# 04_BLE_WIFI_module.net
KiCad netlist of a schematic drawn in Altium Designer
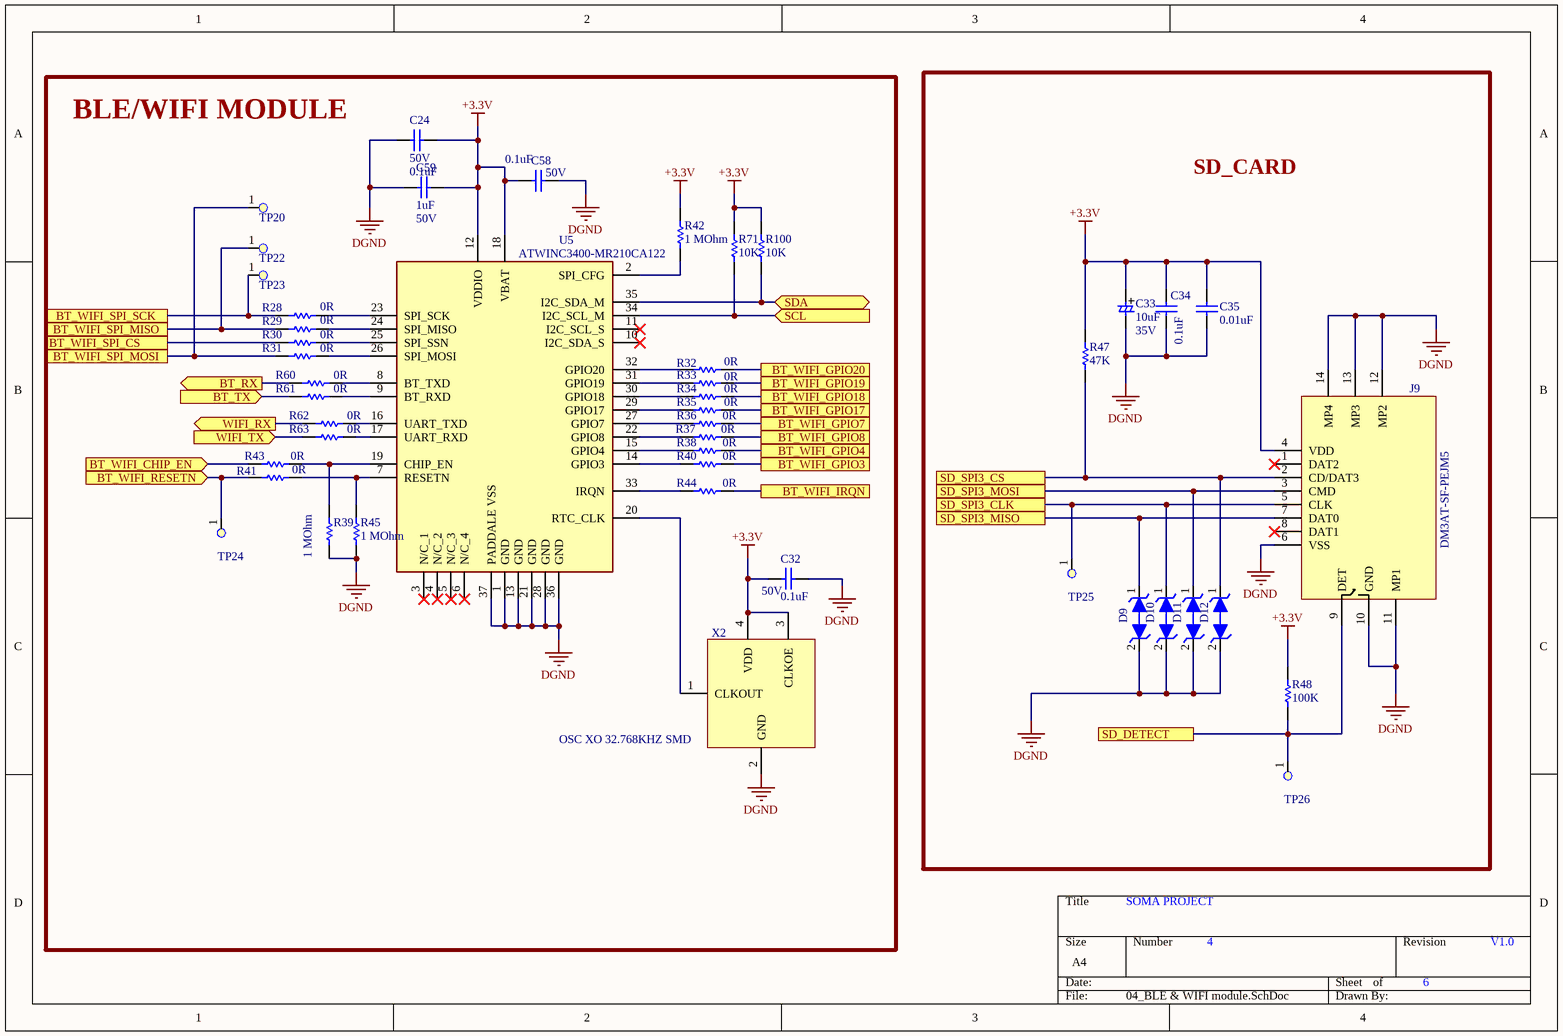
[diagram p0: 04_BLE & WIFI module.SchDoc]

(export (version "E")
  (design (tool "Eeschema 10.0.6"))
  (components
    (comp (ref "C24")
      (value "0.1uF")
      (footprint "C0402")
      (description "CAP CER 0.1UF 50V X7R 0402")
      (fields
        (field (name "MANUFACTURER") "AVX")
        (field (name "DISTRIBUTOR PART NUMBER") "581-04025C104KAT2A")
        (field (name "RATING") "50V")
      )
      (libsource (lib "SOMA_15072021") (part "CAP CER 0.1UF 50V X7R 0402"))
    )
    (comp (ref "C32")
      (value "0.1uF")
      (footprint "C0402")
      (description "CAP CER 0.1UF 50V X7R 0402")
      (fields
        (field (name "MANUFACTURER") "AVX")
        (field (name "DISTRIBUTOR PART NUMBER") "581-04025C104KAT2A")
        (field (name "RATING") "50V")
      )
      (libsource (lib "SOMA_15072021") (part "CAP CER 0.1UF 50V X7R 0402"))
    )
    (comp (ref "C33")
      (value "10uF")
      (footprint "CAPAE430X540N")
      (description "CAP ALUM 10UF 20% 35V SMD")
      (fields
        (field (name "MANUFACTURER") "Panasonic")
        (field (name "MANUFACTURER PART NUMBER") "EEE-1VA100WR")
        (field (name "RATING") "35V")
      )
      (libsource (lib "SOMA_15072021") (part "CAP ALUM 10UF 20% 35V SMD"))
    )
    (comp (ref "C34")
      (value "0.1uF")
      (footprint "C0603")
      (description "CAP CER 0.1UF 10V X7R 0603")
      (fields
        (field (name "MANUFACTURER") "Würth Elektronik")
        (field (name "DISTRIBUTOR PART NUMBER") "732-7939-1-ND")
      )
      (libsource (lib "SOMA_1") (part "CAP CER 0.1UF 10V X7R 0603"))
    )
    (comp (ref "C35")
      (value "0.01uF")
      (footprint "C0402")
      (description "CAP CER 0.01uF 50V X7R 0402")
      (fields
        (field (name "MANUFACTURER") "Yageo")
        (field (name "MANUFACTURER PART NUMBER") "CC0402KRX7R9BB103")
      )
      (libsource (lib "SOMA_15072021") (part "CAP CER 0.01uF 50V X7R 0402"))
    )
    (comp (ref "C58")
      (value "0.1uF")
      (footprint "C0402")
      (description "CAP CER 0.1UF 50V X7R 0402")
      (fields
        (field (name "MANUFACTURER") "AVX")
        (field (name "DISTRIBUTOR PART NUMBER") "581-04025C104KAT2A")
        (field (name "RATING") "50V")
      )
      (libsource (lib "SOMA_15072021") (part "CAP CER 0.1UF 50V X7R 0402"))
    )
    (comp (ref "C59")
      (value "1uF")
      (footprint "C0603")
      (description "CAP CER 1UF 50V X5R 0603")
      (fields
        (field (name "MANUFACTURER") "Taiyo Yuden")
        (field (name "DISTRIBUTOR PART NUMBER") "587-2400-2-ND")
        (field (name "RATING") "50V")
      )
      (libsource (lib "SOMA_15072021") (part "CAP CER 1UF 50V X5R 0603"))
    )
    (comp (ref "D9")
      (value "TVS DIODE 3.3VWM 11.5VC SOD923")
      (footprint "SOD1006X40N_BI")
      (description "11.5V Clamp 2A (8/20µs) Ipp Tvs Diode Surface Mount SOD-923")
      (fields
        (field (name "MANUFACTURER PART NUMBER") "ESD9B3.3ST5G")
        (field (name "MANUFACTURER") "ON Semiconductor")
      )
      (libsource (lib "SOMA_15072021") (part "TVS DIODE 3.3VWM 11.5VC SOD923"))
    )
    (comp (ref "D10")
      (value "TVS DIODE 3.3VWM 11.5VC SOD923")
      (footprint "SOD1006X40N_BI")
      (description "11.5V Clamp 2A (8/20µs) Ipp Tvs Diode Surface Mount SOD-923")
      (fields
        (field (name "MANUFACTURER PART NUMBER") "ESD9B3.3ST5G")
        (field (name "MANUFACTURER") "ON Semiconductor")
      )
      (libsource (lib "SOMA_15072021") (part "TVS DIODE 3.3VWM 11.5VC SOD923"))
    )
    (comp (ref "D11")
      (value "TVS DIODE 3.3VWM 11.5VC SOD923")
      (footprint "SOD1006X40N_BI")
      (description "11.5V Clamp 2A (8/20µs) Ipp Tvs Diode Surface Mount SOD-923")
      (fields
        (field (name "MANUFACTURER PART NUMBER") "ESD9B3.3ST5G")
        (field (name "MANUFACTURER") "ON Semiconductor")
      )
      (libsource (lib "SOMA_15072021") (part "TVS DIODE 3.3VWM 11.5VC SOD923"))
    )
    (comp (ref "D12")
      (value "TVS DIODE 3.3VWM 11.5VC SOD923")
      (footprint "SOD1006X40N_BI")
      (description "11.5V Clamp 2A (8/20µs) Ipp Tvs Diode Surface Mount SOD-923")
      (fields
        (field (name "MANUFACTURER PART NUMBER") "ESD9B3.3ST5G")
        (field (name "MANUFACTURER") "ON Semiconductor")
      )
      (libsource (lib "SOMA_15072021") (part "TVS DIODE 3.3VWM 11.5VC SOD923"))
    )
    (comp (ref "J9")
      (value "DM3AT-SF-PEJM5")
      (footprint "HIROSE_DM3AT-SF-PEJM5")
      (description "CONN MICRO SD CARD PUSH-PUSH R/A")
      (fields
        (field (name "DISTRIBUTOR PART NUMBER") "HR1964CT-ND")
        (field (name "MANUFACTURER") "Hirose Electric Co Ltd")
      )
      (libsource (lib "SOMA_15072021") (part "CONN MICRO SD CARD PUSH-PUSH R/A"))
    )
    (comp (ref "R28")
      (value "0R")
      (footprint "R0402")
      (description "0 Ohms Jumper 0.063W, 1/16W Chip Resistor 0402 (1005 Metric) Moisture Resistant Thick Film")
      (fields (field (name "MANUFACTURER") "Yageo") (field (name "DISTRIBUTOR PART NUMBER") "YAG1279TR-ND"))
      (libsource (lib "SOMA_1") (part "RES SMD 0 OHM JUMPER 1/16W 0402"))
    )
    (comp (ref "R29")
      (value "0R")
      (footprint "R0402")
      (description "0 Ohms Jumper 0.063W, 1/16W Chip Resistor 0402 (1005 Metric) Moisture Resistant Thick Film")
      (fields (field (name "MANUFACTURER") "Yageo") (field (name "DISTRIBUTOR PART NUMBER") "YAG1279TR-ND"))
      (libsource (lib "SOMA_1") (part "RES SMD 0 OHM JUMPER 1/16W 0402"))
    )
    (comp (ref "R30")
      (value "0R")
      (footprint "R0402")
      (description "0 Ohms Jumper 0.063W, 1/16W Chip Resistor 0402 (1005 Metric) Moisture Resistant Thick Film")
      (fields (field (name "MANUFACTURER") "Yageo") (field (name "DISTRIBUTOR PART NUMBER") "YAG1279TR-ND"))
      (libsource (lib "SOMA_1") (part "RES SMD 0 OHM JUMPER 1/16W 0402"))
    )
    (comp (ref "R31")
      (value "0R")
      (footprint "R0402")
      (description "0 Ohms Jumper 0.063W, 1/16W Chip Resistor 0402 (1005 Metric) Moisture Resistant Thick Film")
      (fields (field (name "MANUFACTURER") "Yageo") (field (name "DISTRIBUTOR PART NUMBER") "YAG1279TR-ND"))
      (libsource (lib "SOMA_1") (part "RES SMD 0 OHM JUMPER 1/16W 0402"))
    )
    (comp (ref "R32")
      (value "0R")
      (footprint "R0402")
      (description "0 Ohms Jumper 0.063W, 1/16W Chip Resistor 0402 (1005 Metric) Moisture Resistant Thick Film")
      (fields (field (name "MANUFACTURER") "Yageo") (field (name "DISTRIBUTOR PART NUMBER") "YAG1279TR-ND"))
      (libsource (lib "SOMA_1") (part "RES SMD 0 OHM JUMPER 1/16W 0402"))
    )
    (comp (ref "R33")
      (value "0R")
      (footprint "R0402")
      (description "0 Ohms Jumper 0.063W, 1/16W Chip Resistor 0402 (1005 Metric) Moisture Resistant Thick Film")
      (fields (field (name "MANUFACTURER") "Yageo") (field (name "DISTRIBUTOR PART NUMBER") "YAG1279TR-ND"))
      (libsource (lib "SOMA_1") (part "RES SMD 0 OHM JUMPER 1/16W 0402"))
    )
    (comp (ref "R34")
      (value "0R")
      (footprint "R0402")
      (description "0 Ohms Jumper 0.063W, 1/16W Chip Resistor 0402 (1005 Metric) Moisture Resistant Thick Film")
      (fields (field (name "MANUFACTURER") "Yageo") (field (name "DISTRIBUTOR PART NUMBER") "YAG1279TR-ND"))
      (libsource (lib "SOMA_1") (part "RES SMD 0 OHM JUMPER 1/16W 0402"))
    )
    (comp (ref "R35")
      (value "0R")
      (footprint "R0402")
      (description "0 Ohms Jumper 0.063W, 1/16W Chip Resistor 0402 (1005 Metric) Moisture Resistant Thick Film")
      (fields (field (name "MANUFACTURER") "Yageo") (field (name "DISTRIBUTOR PART NUMBER") "YAG1279TR-ND"))
      (libsource (lib "SOMA_1") (part "RES SMD 0 OHM JUMPER 1/16W 0402"))
    )
    (comp (ref "R36")
      (value "0R")
      (footprint "R0402")
      (description "0 Ohms Jumper 0.063W, 1/16W Chip Resistor 0402 (1005 Metric) Moisture Resistant Thick Film")
      (fields (field (name "MANUFACTURER") "Yageo") (field (name "DISTRIBUTOR PART NUMBER") "YAG1279TR-ND"))
      (libsource (lib "SOMA_1") (part "RES SMD 0 OHM JUMPER 1/16W 0402"))
    )
    (comp (ref "R37")
      (value "0R")
      (footprint "R0402")
      (description "0 Ohms Jumper 0.063W, 1/16W Chip Resistor 0402 (1005 Metric) Moisture Resistant Thick Film")
      (fields (field (name "MANUFACTURER") "Yageo") (field (name "DISTRIBUTOR PART NUMBER") "YAG1279TR-ND"))
      (libsource (lib "SOMA_1") (part "RES SMD 0 OHM JUMPER 1/16W 0402"))
    )
    (comp (ref "R38")
      (value "0R")
      (footprint "R0402")
      (description "0 Ohms Jumper 0.063W, 1/16W Chip Resistor 0402 (1005 Metric) Moisture Resistant Thick Film")
      (fields (field (name "MANUFACTURER") "Yageo") (field (name "DISTRIBUTOR PART NUMBER") "YAG1279TR-ND"))
      (libsource (lib "SOMA_1") (part "RES SMD 0 OHM JUMPER 1/16W 0402"))
    )
    (comp (ref "R39")
      (value "1 MOhm")
      (footprint "R0603")
      (description "RES 1M OHM 1% 1/10W 0603")
      (fields
        (field (name "MANUFACTURER PART NUMBER") "RC0603FR-131ML")
        (field (name "MANUFACTURER") "Yageo")
      )
      (libsource (lib "SOMA_1") (part "RES 1M OHM 1% 1/10W 0603"))
    )
    (comp (ref "R40")
      (value "0R")
      (footprint "R0402")
      (description "0 Ohms Jumper 0.063W, 1/16W Chip Resistor 0402 (1005 Metric) Moisture Resistant Thick Film")
      (fields (field (name "MANUFACTURER") "Yageo") (field (name "DISTRIBUTOR PART NUMBER") "YAG1279TR-ND"))
      (libsource (lib "SOMA_1") (part "RES SMD 0 OHM JUMPER 1/16W 0402"))
    )
    (comp (ref "R41")
      (value "0R")
      (footprint "R0402")
      (description "0 Ohms Jumper 0.063W, 1/16W Chip Resistor 0402 (1005 Metric) Moisture Resistant Thick Film")
      (fields (field (name "MANUFACTURER") "Yageo") (field (name "DISTRIBUTOR PART NUMBER") "YAG1279TR-ND"))
      (libsource (lib "SOMA_1") (part "RES SMD 0 OHM JUMPER 1/16W 0402"))
    )
    (comp (ref "R42")
      (value "1 MOhm")
      (footprint "R0603")
      (description "RES 1M OHM 1% 1/10W 0603")
      (fields
        (field (name "MANUFACTURER PART NUMBER") "RC0603FR-131ML")
        (field (name "MANUFACTURER") "Yageo")
      )
      (libsource (lib "SOMA_1") (part "RES 1M OHM 1% 1/10W 0603"))
    )
    (comp (ref "R43")
      (value "0R")
      (footprint "R0402")
      (description "0 Ohms Jumper 0.063W, 1/16W Chip Resistor 0402 (1005 Metric) Moisture Resistant Thick Film")
      (fields (field (name "MANUFACTURER") "Yageo") (field (name "DISTRIBUTOR PART NUMBER") "YAG1279TR-ND"))
      (libsource (lib "SOMA_1") (part "RES SMD 0 OHM JUMPER 1/16W 0402"))
    )
    (comp (ref "R44")
      (value "0R")
      (footprint "R0402")
      (description "0 Ohms Jumper 0.063W, 1/16W Chip Resistor 0402 (1005 Metric) Moisture Resistant Thick Film")
      (fields (field (name "MANUFACTURER") "Yageo") (field (name "DISTRIBUTOR PART NUMBER") "YAG1279TR-ND"))
      (libsource (lib "SOMA_1") (part "RES SMD 0 OHM JUMPER 1/16W 0402"))
    )
    (comp (ref "R45")
      (value "1 MOhm")
      (footprint "R0603")
      (description "RES 1M OHM 1% 1/10W 0603")
      (fields
        (field (name "MANUFACTURER PART NUMBER") "RC0603FR-131ML")
        (field (name "MANUFACTURER") "Yageo")
      )
      (libsource (lib "SOMA_1") (part "RES 1M OHM 1% 1/10W 0603"))
    )
    (comp (ref "R47")
      (value "47K")
      (footprint "R0402")
      (description "RES SMD 47K OHM 5% 1/10W 0402")
      (fields
        (field (name "MANUFACTURER PART NUMBER") "ERJ-2GEJ473X")
        (field (name "DISTRIBUTOR PART NUMBER") "P47KJCT-ND")
      )
      (libsource (lib "SOMA_15072021") (part "RES SMD 47K OHM 5% 1/10W 0402"))
    )
    (comp (ref "R48")
      (value "100K")
      (footprint "R0402")
      (description "100 kOhms ±1% 0.1W, 1/10W Chip Resistor 0402 (1005 Metric) Automotive AEC-Q200 Thick Film")
      (fields
        (field (name "MANUFACTURER") "Panasonic Electronic Components")
        (field (name "MANUFACTURER PART NUMBER") "ERJ-2RKF1003X")
      )
      (libsource (lib "SOMA_15072021") (part "RES SMD 100K OHM 1% 1/10W 0402"))
    )
    (comp (ref "R60")
      (value "0R")
      (footprint "R0402")
      (description "0 Ohms Jumper 0.063W, 1/16W Chip Resistor 0402 (1005 Metric) Moisture Resistant Thick Film")
      (fields (field (name "MANUFACTURER") "Yageo") (field (name "DISTRIBUTOR PART NUMBER") "YAG1279TR-ND"))
      (libsource (lib "SOMA_1") (part "RES SMD 0 OHM JUMPER 1/16W 0402"))
    )
    (comp (ref "R61")
      (value "0R")
      (footprint "R0402")
      (description "0 Ohms Jumper 0.063W, 1/16W Chip Resistor 0402 (1005 Metric) Moisture Resistant Thick Film")
      (fields (field (name "MANUFACTURER") "Yageo") (field (name "DISTRIBUTOR PART NUMBER") "YAG1279TR-ND"))
      (libsource (lib "SOMA_1") (part "RES SMD 0 OHM JUMPER 1/16W 0402"))
    )
    (comp (ref "R62")
      (value "0R")
      (footprint "R0402")
      (description "0 Ohms Jumper 0.063W, 1/16W Chip Resistor 0402 (1005 Metric) Moisture Resistant Thick Film")
      (fields (field (name "MANUFACTURER") "Yageo") (field (name "DISTRIBUTOR PART NUMBER") "YAG1279TR-ND"))
      (libsource (lib "SOMA_1") (part "RES SMD 0 OHM JUMPER 1/16W 0402"))
    )
    (comp (ref "R63")
      (value "0R")
      (footprint "R0402")
      (description "0 Ohms Jumper 0.063W, 1/16W Chip Resistor 0402 (1005 Metric) Moisture Resistant Thick Film")
      (fields (field (name "MANUFACTURER") "Yageo") (field (name "DISTRIBUTOR PART NUMBER") "YAG1279TR-ND"))
      (libsource (lib "SOMA_1") (part "RES SMD 0 OHM JUMPER 1/16W 0402"))
    )
    (comp (ref "R71")
      (value "10K")
      (footprint "R0402")
      (description "10 kOhms ±1% 0.1W, 1/10W Chip Resistor 0402 (1005 Metric) Automotive AEC-Q200 Thick Film")
      (fields
        (field (name "MANUFACTURER") "Panasonic Electronic Components")
        (field (name "DISTRIBUTOR PART NUMBER") "P10.0KLCT-ND")
      )
      (libsource (lib "Daughtercard_Library") (part "RES SMD 10K OHM 1% 1/10W 0402"))
    )
    (comp (ref "R100")
      (value "10K")
      (footprint "R0402")
      (description "10 kOhms ±1% 0.1W, 1/10W Chip Resistor 0402 (1005 Metric) Automotive AEC-Q200 Thick Film")
      (fields
        (field (name "MANUFACTURER") "Panasonic Electronic Components")
        (field (name "DISTRIBUTOR PART NUMBER") "P10.0KLCT-ND")
      )
      (libsource (lib "Daughtercard_Library") (part "RES SMD 10K OHM 1% 1/10W 0402"))
    )
    (comp (ref "TP20")
      (value "Test Point,1.6mm Diameter,SMD")
      (footprint "TP_63C")
      (libsource (lib "SOMA_1") (part "Test Point,1.6mm Diameter,SMD"))
    )
    (comp (ref "TP22")
      (value "Test Point,1.6mm Diameter,SMD")
      (footprint "TP_63C")
      (libsource (lib "SOMA_1") (part "Test Point,1.6mm Diameter,SMD"))
    )
    (comp (ref "TP23")
      (value "Test Point,1.6mm Diameter,SMD")
      (footprint "TP_63C")
      (libsource (lib "SOMA_1") (part "Test Point,1.6mm Diameter,SMD"))
    )
    (comp (ref "TP24")
      (value "Test Point,1.6mm Diameter,SMD")
      (footprint "TP_63C")
      (libsource (lib "SOMA_1") (part "Test Point,1.6mm Diameter,SMD"))
    )
    (comp (ref "TP25")
      (value "Test Point,1.6mm Diameter,SMD")
      (footprint "TP_63C")
      (libsource (lib "SOMA_1") (part "Test Point,1.6mm Diameter,SMD"))
    )
    (comp (ref "TP26")
      (value "Test Point,1.6mm Diameter,SMD")
      (footprint "TP_63C")
      (libsource (lib "SOMA_1") (part "Test Point,1.6mm Diameter,SMD"))
    )
    (comp (ref "U5")
      (value "ATWINC3400-MR210CA122")
      (footprint "MICROCHIP_ATWINC3400-MR210xA")
      (description "RX TXRX MODULE WIFI CHIP SMD")
      (fields
        (field (name "MANUFACTURER") "Microchip Technology")
        (field (name "DISTRIBUTOR PART NUMBER") "ATWINC3400-MR210CA122-ND")
      )
      (libsource (lib "SOMA_15072021") (part "RX TXRX MODULE WIFI CHIP SMD"))
    )
    (comp (ref "X2")
      (value "OSC XO 32.768KHZ SMD")
      (footprint "XTAL320X150X70-4N")
      (description "32.768 kHz XO (Standard) CMOS Oscillator 1.2V ~ 5.5V Enable/Disable 4-SMD, No Lead")
      (fields
        (field (name "MANUFACTURER") "Micro Crystal AG")
        (field (name "MANUFACTURER PART NUMBER") "OM-7604-C7-32.768KHZ-20PPM-TA-QC")
      )
      (libsource (lib "SOMA_1") (part "OSC XO 32.768KHZ SMD"))
    )
  )
  (nets
    (net (code "1") (name "+3.3V") (class "Default")
      (node (ref "C24") (pin "1") (pinfunction "1_1") (pintype "passive"))
      (node (ref "C32") (pin "2") (pinfunction "2_2") (pintype "passive"))
      (node (ref "C33") (pin "2") (pinfunction "2_2") (pintype "passive"))
      (node (ref "C34") (pin "2") (pinfunction "2_2") (pintype "passive"))
      (node (ref "C35") (pin "2") (pinfunction "2_2") (pintype "passive"))
      (node (ref "C58") (pin "2") (pinfunction "2_2") (pintype "passive"))
      (node (ref "C59") (pin "1") (pinfunction "1_1") (pintype "passive"))
      (node (ref "J9") (pin "4") (pinfunction "VDD_4") (pintype "passive"))
      (node (ref "R100") (pin "2") (pinfunction "2_2") (pintype "passive"))
      (node (ref "R42") (pin "1") (pinfunction "1_1") (pintype "passive"))
      (node (ref "R47") (pin "2") (pinfunction "2_2") (pintype "passive"))
      (node (ref "R48") (pin "2") (pinfunction "2_2") (pintype "passive"))
      (node (ref "R71") (pin "2") (pinfunction "2_2") (pintype "passive"))
      (node (ref "U5") (pin "12") (pinfunction "VDDIO_12") (pintype "power_in"))
      (node (ref "U5") (pin "18") (pinfunction "VBAT_18") (pintype "power_in"))
      (node (ref "X2") (pin "3") (pinfunction "CLKOE_3") (pintype "passive"))
      (node (ref "X2") (pin "4") (pinfunction "VDD_4") (pintype "passive"))
    )
    (net (code "2") (name "/BT_RX") (class "Default")
      (node (ref "R60") (pin "1") (pinfunction "1_1") (pintype "passive"))
    )
    (net (code "3") (name "/BT_TX") (class "Default")
      (node (ref "R61") (pin "1") (pinfunction "1_1") (pintype "passive"))
    )
    (net (code "4") (name "/BT_WIFI_CHIP_EN") (class "Default")
      (node (ref "R43") (pin "1") (pinfunction "1_1") (pintype "passive"))
    )
    (net (code "5") (name "/BT_WIFI_GPIO3") (class "Default")
      (node (ref "R40") (pin "2") (pinfunction "2_2") (pintype "passive"))
    )
    (net (code "6") (name "/BT_WIFI_GPIO4") (class "Default")
      (node (ref "R38") (pin "2") (pinfunction "2_2") (pintype "passive"))
    )
    (net (code "7") (name "/BT_WIFI_GPIO7") (class "Default")
      (node (ref "R36") (pin "2") (pinfunction "2_2") (pintype "passive"))
    )
    (net (code "8") (name "/BT_WIFI_GPIO8") (class "Default")
      (node (ref "R37") (pin "2") (pinfunction "2_2") (pintype "passive"))
    )
    (net (code "9") (name "/BT_WIFI_GPIO17") (class "Default")
      (node (ref "R35") (pin "2") (pinfunction "2_2") (pintype "passive"))
    )
    (net (code "10") (name "/BT_WIFI_GPIO18") (class "Default")
      (node (ref "R34") (pin "2") (pinfunction "2_2") (pintype "passive"))
    )
    (net (code "11") (name "/BT_WIFI_GPIO19") (class "Default")
      (node (ref "R33") (pin "2") (pinfunction "2_2") (pintype "passive"))
    )
    (net (code "12") (name "/BT_WIFI_GPIO20") (class "Default")
      (node (ref "R32") (pin "2") (pinfunction "2_2") (pintype "passive"))
    )
    (net (code "13") (name "/BT_WIFI_IRQN") (class "Default")
      (node (ref "R44") (pin "2") (pinfunction "2_2") (pintype "passive"))
    )
    (net (code "14") (name "/BT_WIFI_RESETN") (class "Default")
      (node (ref "R41") (pin "1") (pinfunction "1_1") (pintype "passive"))
      (node (ref "TP24") (pin "1") (pinfunction "0_1") (pintype "passive"))
    )
    (net (code "15") (name "/BT_WIFI_SPI_CS") (class "Default")
      (node (ref "R30") (pin "1") (pinfunction "1_1") (pintype "passive"))
    )
    (net (code "16") (name "/BT_WIFI_SPI_MISO") (class "Default")
      (node (ref "R29") (pin "1") (pinfunction "1_1") (pintype "passive"))
      (node (ref "TP22") (pin "1") (pinfunction "0_1") (pintype "passive"))
    )
    (net (code "17") (name "/BT_WIFI_SPI_MOSI") (class "Default")
      (node (ref "R31") (pin "1") (pinfunction "1_1") (pintype "passive"))
      (node (ref "TP20") (pin "1") (pinfunction "0_1") (pintype "passive"))
    )
    (net (code "18") (name "/BT_WIFI_SPI_SCK") (class "Default")
      (node (ref "R28") (pin "1") (pinfunction "1_1") (pintype "passive"))
      (node (ref "TP23") (pin "1") (pinfunction "0_1") (pintype "passive"))
    )
    (net (code "19") (name "/SCL") (class "Default")
      (node (ref "R71") (pin "1") (pinfunction "1_1") (pintype "passive"))
      (node (ref "U5") (pin "34") (pinfunction "I2C_SCL_M_34") (pintype "passive"))
    )
    (net (code "20") (name "/SDA") (class "Default")
      (node (ref "R100") (pin "1") (pinfunction "1_1") (pintype "passive"))
      (node (ref "U5") (pin "35") (pinfunction "I2C_SDA_M_35") (pintype "passive"))
    )
    (net (code "21") (name "/SD_DETECT") (class "Default")
      (node (ref "J9") (pin "9") (pinfunction "DET_9") (pintype "passive"))
      (node (ref "R48") (pin "1") (pinfunction "1_1") (pintype "passive"))
      (node (ref "TP26") (pin "1") (pinfunction "0_1") (pintype "passive"))
    )
    (net (code "22") (name "/SD_SPI3_CLK") (class "Default")
      (node (ref "D10") (pin "1") (pinfunction "K_1") (pintype "passive"))
      (node (ref "J9") (pin "5") (pinfunction "CLK_5") (pintype "passive"))
      (node (ref "TP25") (pin "1") (pinfunction "0_1") (pintype "passive"))
    )
    (net (code "23") (name "/SD_SPI3_CS") (class "Default")
      (node (ref "D12") (pin "1") (pinfunction "K_1") (pintype "passive"))
      (node (ref "J9") (pin "2") (pinfunction "CD/DAT3_2") (pintype "passive"))
      (node (ref "R47") (pin "1") (pinfunction "1_1") (pintype "passive"))
    )
    (net (code "24") (name "/SD_SPI3_MISO") (class "Default")
      (node (ref "D9") (pin "1") (pinfunction "K_1") (pintype "passive"))
      (node (ref "J9") (pin "7") (pinfunction "DAT0_7") (pintype "passive"))
    )
    (net (code "25") (name "/SD_SPI3_MOSI") (class "Default")
      (node (ref "D11") (pin "1") (pinfunction "K_1") (pintype "passive"))
      (node (ref "J9") (pin "3") (pinfunction "CMD_3") (pintype "passive"))
    )
    (net (code "26") (name "/WIFI_RX") (class "Default")
      (node (ref "R62") (pin "1") (pinfunction "1_1") (pintype "passive"))
    )
    (net (code "27") (name "/WIFI_TX") (class "Default")
      (node (ref "R63") (pin "1") (pinfunction "1_1") (pintype "passive"))
    )
    (net (code "28") (name "DGND") (class "Default")
      (node (ref "C24") (pin "2") (pinfunction "2_2") (pintype "passive"))
      (node (ref "C32") (pin "1") (pinfunction "1_1") (pintype "passive"))
      (node (ref "C33") (pin "1") (pinfunction "1_1") (pintype "passive"))
      (node (ref "C34") (pin "1") (pinfunction "1_1") (pintype "passive"))
      (node (ref "C35") (pin "1") (pinfunction "1_1") (pintype "passive"))
      (node (ref "C58") (pin "1") (pinfunction "1_1") (pintype "passive"))
      (node (ref "C59") (pin "2") (pinfunction "2_2") (pintype "passive"))
      (node (ref "D10") (pin "2") (pinfunction "A_2") (pintype "passive"))
      (node (ref "D11") (pin "2") (pinfunction "A_2") (pintype "passive"))
      (node (ref "D12") (pin "2") (pinfunction "A_2") (pintype "passive"))
      (node (ref "D9") (pin "2") (pinfunction "A_2") (pintype "passive"))
      (node (ref "J9") (pin "10") (pinfunction "GND_10") (pintype "passive"))
      (node (ref "J9") (pin "11") (pinfunction "MP1_11") (pintype "passive"))
      (node (ref "J9") (pin "12") (pinfunction "MP2_12") (pintype "passive"))
      (node (ref "J9") (pin "13") (pinfunction "MP3_13") (pintype "passive"))
      (node (ref "J9") (pin "14") (pinfunction "MP4_14") (pintype "passive"))
      (node (ref "J9") (pin "6") (pinfunction "VSS_6") (pintype "passive"))
      (node (ref "R39") (pin "2") (pinfunction "2_2") (pintype "passive"))
      (node (ref "R45") (pin "1") (pinfunction "1_1") (pintype "passive"))
      (node (ref "U5") (pin "1") (pinfunction "GND_1") (pintype "passive"))
      (node (ref "U5") (pin "13") (pinfunction "GND_13") (pintype "passive"))
      (node (ref "U5") (pin "21") (pinfunction "GND_21") (pintype "passive"))
      (node (ref "U5") (pin "28") (pinfunction "GND_28") (pintype "passive"))
      (node (ref "U5") (pin "36") (pinfunction "GND_36") (pintype "passive"))
      (node (ref "U5") (pin "37") (pinfunction "PADDALE_VSS_37") (pintype "passive"))
      (node (ref "X2") (pin "2") (pinfunction "GND_2") (pintype "passive"))
    )
    (net (code "29") (name "Net-(U5-BT_RXD)") (class "Default")
      (node (ref "R61") (pin "2") (pinfunction "2_2") (pintype "passive"))
      (node (ref "U5") (pin "9") (pinfunction "BT_RXD_9") (pintype "passive"))
    )
    (net (code "30") (name "Net-(U5-BT_TXD)") (class "Default")
      (node (ref "R60") (pin "2") (pinfunction "2_2") (pintype "passive"))
      (node (ref "U5") (pin "8") (pinfunction "BT_TXD_8") (pintype "passive"))
    )
    (net (code "31") (name "Net-(U5-CHIP_EN)") (class "Default")
      (node (ref "R39") (pin "1") (pinfunction "1_1") (pintype "passive"))
      (node (ref "R43") (pin "2") (pinfunction "2_2") (pintype "passive"))
      (node (ref "U5") (pin "19") (pinfunction "CHIP_EN_19") (pintype "passive"))
    )
    (net (code "32") (name "Net-(U5-GPIO3)") (class "Default")
      (node (ref "R40") (pin "1") (pinfunction "1_1") (pintype "passive"))
      (node (ref "U5") (pin "14") (pinfunction "GPIO3_14") (pintype "passive"))
    )
    (net (code "33") (name "Net-(U5-GPIO4)") (class "Default")
      (node (ref "R38") (pin "1") (pinfunction "1_1") (pintype "passive"))
      (node (ref "U5") (pin "15") (pinfunction "GPIO4_15") (pintype "passive"))
    )
    (net (code "34") (name "Net-(U5-GPIO7)") (class "Default")
      (node (ref "R36") (pin "1") (pinfunction "1_1") (pintype "passive"))
      (node (ref "U5") (pin "27") (pinfunction "GPIO7_27") (pintype "passive"))
    )
    (net (code "35") (name "Net-(U5-GPIO8)") (class "Default")
      (node (ref "R37") (pin "1") (pinfunction "1_1") (pintype "passive"))
      (node (ref "U5") (pin "22") (pinfunction "GPIO8_22") (pintype "passive"))
    )
    (net (code "36") (name "Net-(U5-GPIO17)") (class "Default")
      (node (ref "R35") (pin "1") (pinfunction "1_1") (pintype "passive"))
      (node (ref "U5") (pin "29") (pinfunction "GPIO17_29") (pintype "passive"))
    )
    (net (code "37") (name "Net-(U5-GPIO18)") (class "Default")
      (node (ref "R34") (pin "1") (pinfunction "1_1") (pintype "passive"))
      (node (ref "U5") (pin "30") (pinfunction "GPIO18_30") (pintype "passive"))
    )
    (net (code "38") (name "Net-(U5-GPIO19)") (class "Default")
      (node (ref "R33") (pin "1") (pinfunction "1_1") (pintype "passive"))
      (node (ref "U5") (pin "31") (pinfunction "GPIO19_31") (pintype "passive"))
    )
    (net (code "39") (name "Net-(U5-GPIO20)") (class "Default")
      (node (ref "R32") (pin "1") (pinfunction "1_1") (pintype "passive"))
      (node (ref "U5") (pin "32") (pinfunction "GPIO20_32") (pintype "passive"))
    )
    (net (code "40") (name "Net-(U5-IRQN)") (class "Default")
      (node (ref "R44") (pin "1") (pinfunction "1_1") (pintype "passive"))
      (node (ref "U5") (pin "33") (pinfunction "IRQN_33") (pintype "passive"))
    )
    (net (code "41") (name "Net-(U5-RESETN)") (class "Default")
      (node (ref "R41") (pin "2") (pinfunction "2_2") (pintype "passive"))
      (node (ref "R45") (pin "2") (pinfunction "2_2") (pintype "passive"))
      (node (ref "U5") (pin "7") (pinfunction "RESETN_7") (pintype "passive"))
    )
    (net (code "42") (name "Net-(U5-RTC_CLK)") (class "Default")
      (node (ref "U5") (pin "20") (pinfunction "RTC_CLK_20") (pintype "passive"))
      (node (ref "X2") (pin "1") (pinfunction "CLKOUT_1") (pintype "passive"))
    )
    (net (code "43") (name "Net-(U5-SPI_CFG)") (class "Default")
      (node (ref "R42") (pin "2") (pinfunction "2_2") (pintype "passive"))
      (node (ref "U5") (pin "2") (pinfunction "SPI_CFG_2") (pintype "passive"))
    )
    (net (code "44") (name "Net-(U5-SPI_MISO)") (class "Default")
      (node (ref "R29") (pin "2") (pinfunction "2_2") (pintype "passive"))
      (node (ref "U5") (pin "24") (pinfunction "SPI_MISO_24") (pintype "passive"))
    )
    (net (code "45") (name "Net-(U5-SPI_MOSI)") (class "Default")
      (node (ref "R31") (pin "2") (pinfunction "2_2") (pintype "passive"))
      (node (ref "U5") (pin "26") (pinfunction "SPI_MOSI_26") (pintype "passive"))
    )
    (net (code "46") (name "Net-(U5-SPI_SCK)") (class "Default")
      (node (ref "R28") (pin "2") (pinfunction "2_2") (pintype "passive"))
      (node (ref "U5") (pin "23") (pinfunction "SPI_SCK_23") (pintype "passive"))
    )
    (net (code "47") (name "Net-(U5-SPI_SSN)") (class "Default")
      (node (ref "R30") (pin "2") (pinfunction "2_2") (pintype "passive"))
      (node (ref "U5") (pin "25") (pinfunction "SPI_SSN_25") (pintype "passive"))
    )
    (net (code "48") (name "Net-(U5-UART_RXD)") (class "Default")
      (node (ref "R63") (pin "2") (pinfunction "2_2") (pintype "passive"))
      (node (ref "U5") (pin "17") (pinfunction "UART_RXD_17") (pintype "passive"))
    )
    (net (code "49") (name "Net-(U5-UART_TXD)") (class "Default")
      (node (ref "R62") (pin "2") (pinfunction "2_2") (pintype "passive"))
      (node (ref "U5") (pin "16") (pinfunction "UART_TXD_16") (pintype "passive"))
    )
    (net (code "50") (name "unconnected-(J9-DAT1-Pad8)") (class "Default")
      (node (ref "J9") (pin "8") (pinfunction "DAT1_8") (pintype "passive+no_connect"))
    )
    (net (code "51") (name "unconnected-(J9-DAT2-Pad1)") (class "Default")
      (node (ref "J9") (pin "1") (pinfunction "DAT2_1") (pintype "passive+no_connect"))
    )
    (net (code "52") (name "unconnected-(U5-I2C_SCL_S-Pad11)") (class "Default")
      (node (ref "U5") (pin "11") (pinfunction "I2C_SCL_S_11") (pintype "passive+no_connect"))
    )
    (net (code "53") (name "unconnected-(U5-I2C_SDA_S-Pad10)") (class "Default")
      (node (ref "U5") (pin "10") (pinfunction "I2C_SDA_S_10") (pintype "passive+no_connect"))
    )
    (net (code "54") (name "unconnected-(U5-N{slash}C_1-Pad3)") (class "Default")
      (node (ref "U5") (pin "3") (pinfunction "N/C_1_3") (pintype "passive+no_connect"))
    )
    (net (code "55") (name "unconnected-(U5-N{slash}C_2-Pad4)") (class "Default")
      (node (ref "U5") (pin "4") (pinfunction "N/C_2_4") (pintype "passive+no_connect"))
    )
    (net (code "56") (name "unconnected-(U5-N{slash}C_3-Pad5)") (class "Default")
      (node (ref "U5") (pin "5") (pinfunction "N/C_3_5") (pintype "passive+no_connect"))
    )
    (net (code "57") (name "unconnected-(U5-N{slash}C_4-Pad6)") (class "Default")
      (node (ref "U5") (pin "6") (pinfunction "N/C_4_6") (pintype "passive+no_connect"))
    )
  )
)
